# isp_breadboard.net
KiCad netlist of a schematic drawn in EAGLE
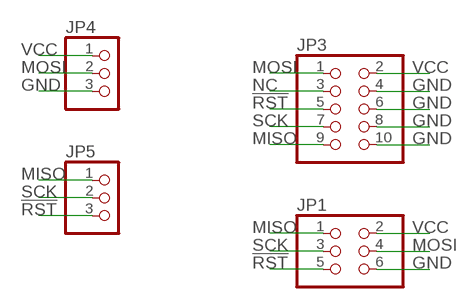
[diagram p0: schematic, sheet 1]

(export (version "E")
  (design (tool "Eeschema 10.0.6"))
  (components
    (comp (ref "JP1")
      (value "PINHD-2X3")
      (footprint "eagle-import:2X03")
      (libsource (lib "eagle-import") (part "PINHD-2X3"))
    )
    (comp (ref "JP3")
      (value "PINHD-2X5")
      (footprint "eagle-import:2X05")
      (libsource (lib "eagle-import") (part "PINHD-2X5"))
    )
    (comp (ref "JP4")
      (value "PINHD-1X3")
      (footprint "eagle-import:1X03")
      (libsource (lib "eagle-import") (part "PINHD-1X3"))
    )
    (comp (ref "JP5")
      (value "PINHD-1X3")
      (footprint "eagle-import:1X03")
      (libsource (lib "eagle-import") (part "PINHD-1X3"))
    )
  )
  (nets
    (net (code "1") (name "/GND") (class "Default")
      (node (ref "JP1") (pin "6") (pinfunction "6_6") (pintype "passive"))
      (node (ref "JP3") (pin "10") (pinfunction "10_10") (pintype "passive"))
      (node (ref "JP3") (pin "4") (pinfunction "4_4") (pintype "passive"))
      (node (ref "JP3") (pin "6") (pinfunction "6_6") (pintype "passive"))
      (node (ref "JP3") (pin "8") (pinfunction "8_8") (pintype "passive"))
      (node (ref "JP4") (pin "3") (pinfunction "3_3") (pintype "passive"))
    )
    (net (code "2") (name "/MISO") (class "Default")
      (node (ref "JP1") (pin "1") (pinfunction "1_1") (pintype "passive"))
      (node (ref "JP3") (pin "9") (pinfunction "9_9") (pintype "passive"))
      (node (ref "JP5") (pin "1") (pinfunction "1_1") (pintype "passive"))
    )
    (net (code "3") (name "/MOSI") (class "Default")
      (node (ref "JP1") (pin "4") (pinfunction "4_4") (pintype "passive"))
      (node (ref "JP3") (pin "1") (pinfunction "1_1") (pintype "passive"))
      (node (ref "JP4") (pin "2") (pinfunction "2_2") (pintype "passive"))
    )
    (net (code "4") (name "/NC") (class "Default")
      (node (ref "JP3") (pin "3") (pinfunction "3_3") (pintype "passive"))
    )
    (net (code "5") (name "/SCK") (class "Default")
      (node (ref "JP1") (pin "3") (pinfunction "3_3") (pintype "passive"))
      (node (ref "JP3") (pin "7") (pinfunction "7_7") (pintype "passive"))
      (node (ref "JP5") (pin "2") (pinfunction "2_2") (pintype "passive"))
    )
    (net (code "6") (name "/VCC") (class "Default")
      (node (ref "JP1") (pin "2") (pinfunction "2_2") (pintype "passive"))
      (node (ref "JP3") (pin "2") (pinfunction "2_2") (pintype "passive"))
      (node (ref "JP4") (pin "1") (pinfunction "1_1") (pintype "passive"))
    )
    (net (code "7") (name "/~{RST}") (class "Default")
      (node (ref "JP1") (pin "5") (pinfunction "5_5") (pintype "passive"))
      (node (ref "JP3") (pin "5") (pinfunction "5_5") (pintype "passive"))
      (node (ref "JP5") (pin "3") (pinfunction "3_3") (pintype "passive"))
    )
  )
)
